# IA-prop-raspberry.net
KiCad netlist of a schematic drawn in EAGLE
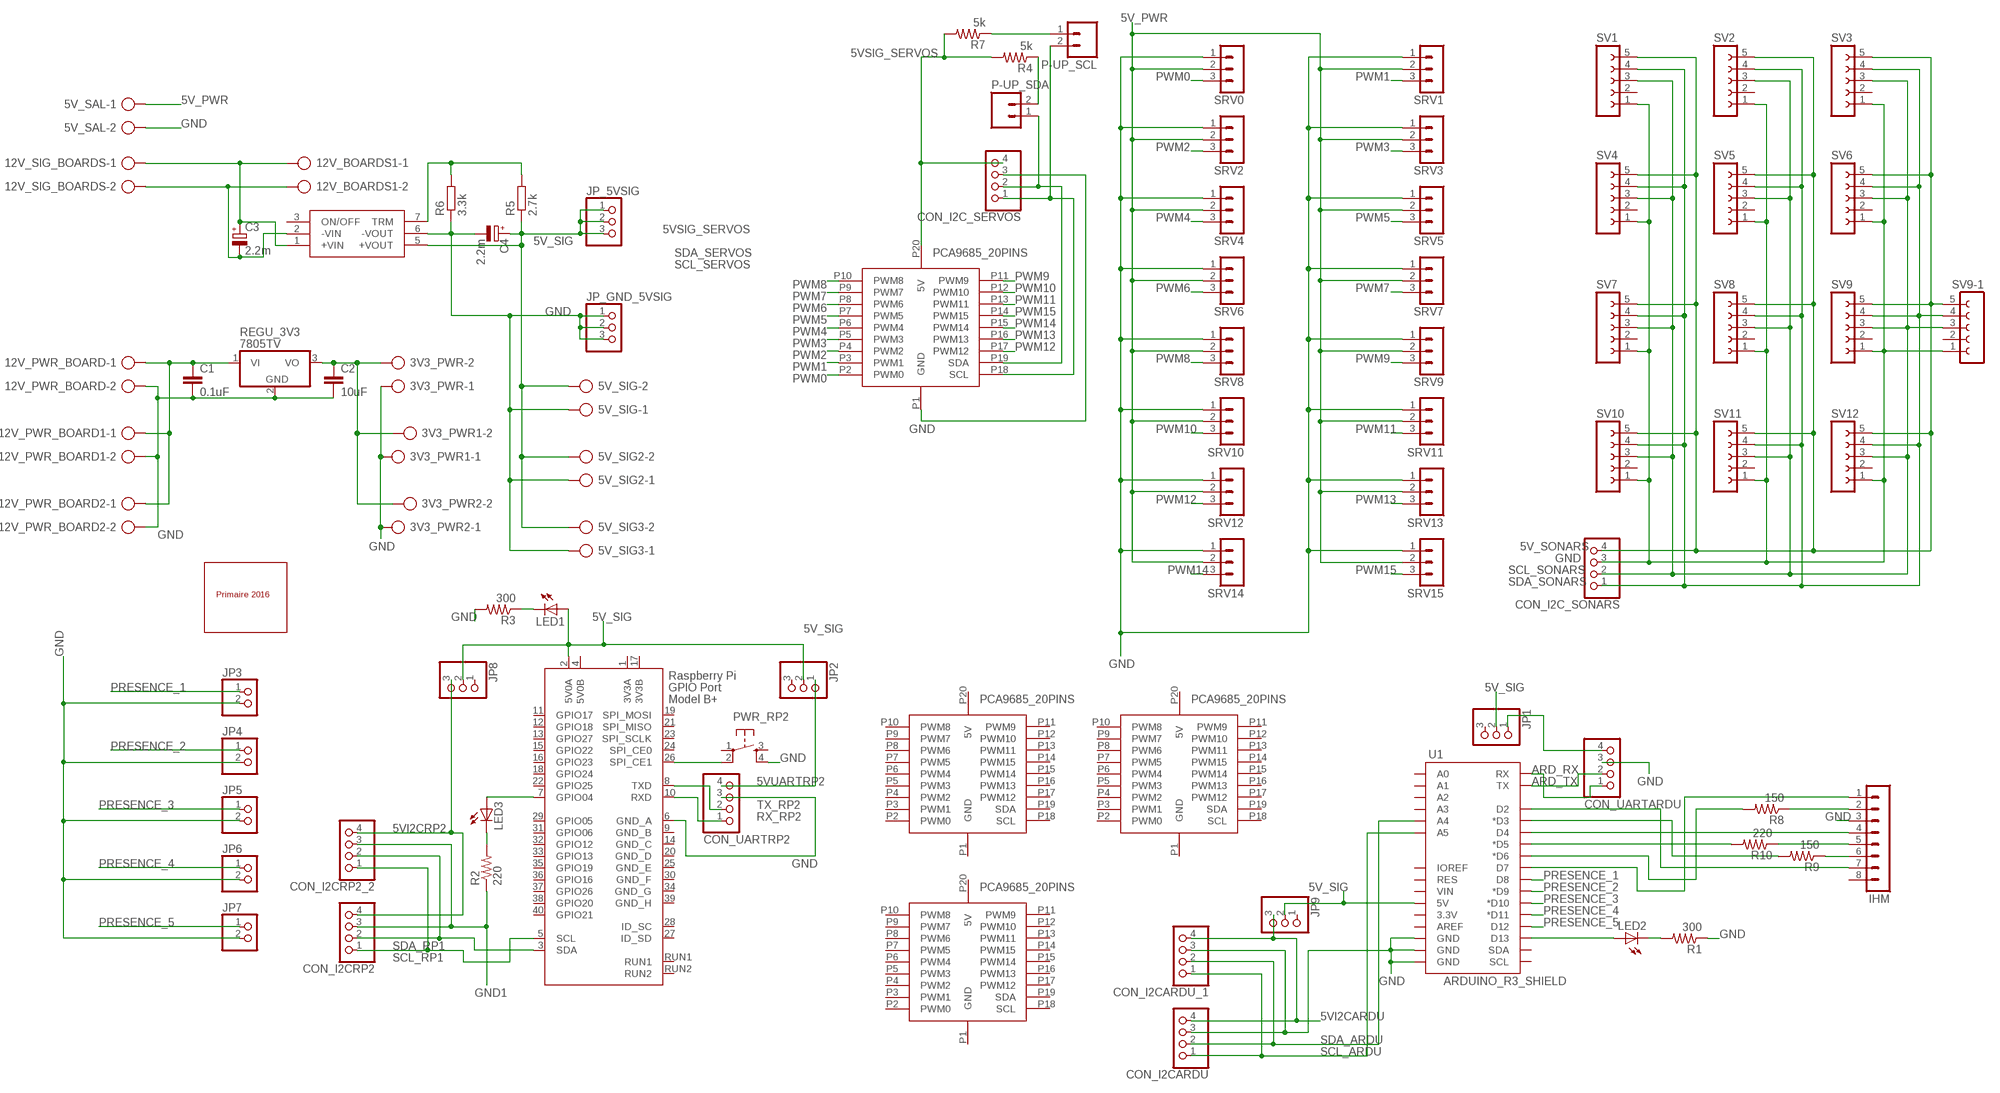
[diagram p0: schematic, sheet 1, part 1 of 2]
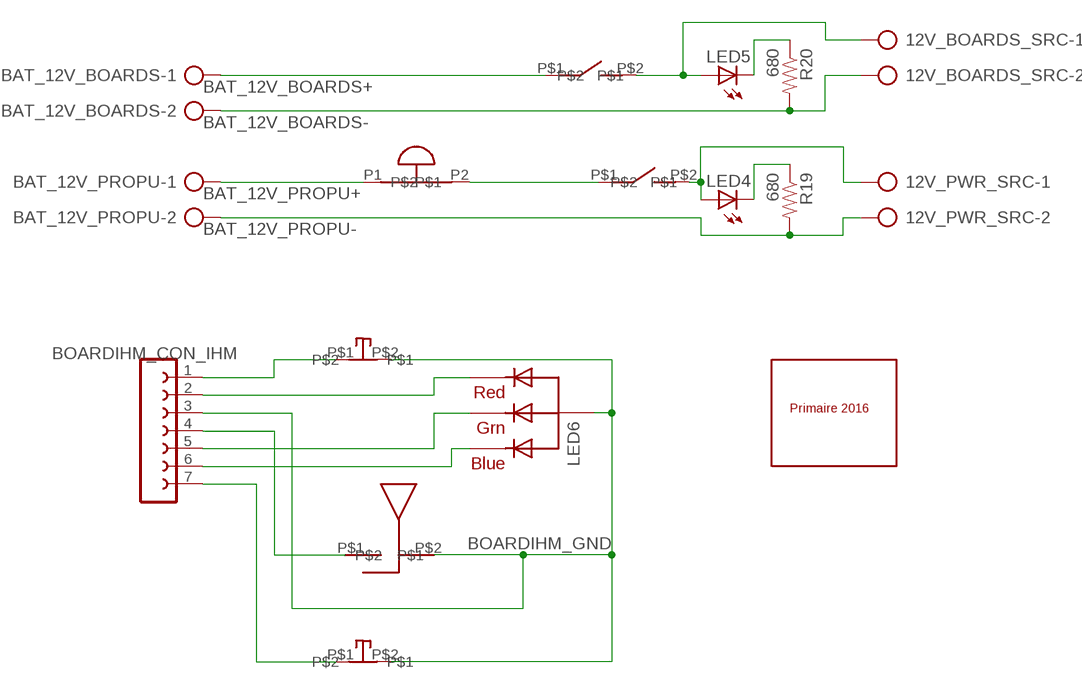
[diagram p1: schematic, sheet 1, part 2 of 2]

(export (version "E")
  (design (tool "Eeschema 10.0.6"))
  (components
    (comp (ref "3V3_PWR")
      (value "AK300/2")
      (footprint "eagle-import:AK300_2")
      (fields (field (name "OC_FARNELL") "unknown") (field (name "OC_NEWARK") "unknown"))
      (libsource (lib "eagle-import") (part "AK300/2"))
    )
    (comp (ref "3V3_PWR1")
      (value "AK300/2")
      (footprint "eagle-import:AK300_2")
      (fields (field (name "OC_FARNELL") "unknown") (field (name "OC_NEWARK") "unknown"))
      (libsource (lib "eagle-import") (part "AK300/2"))
    )
    (comp (ref "3V3_PWR2")
      (value "AK300/2")
      (footprint "eagle-import:AK300_2")
      (fields (field (name "OC_FARNELL") "unknown") (field (name "OC_NEWARK") "unknown"))
      (libsource (lib "eagle-import") (part "AK300/2"))
    )
    (comp (ref "5V_SAL")
      (value "AK300/2")
      (footprint "eagle-import:AK300_2")
      (fields (field (name "OC_FARNELL") "unknown") (field (name "OC_NEWARK") "unknown"))
      (libsource (lib "eagle-import") (part "AK300/2"))
    )
    (comp (ref "5V_SIG")
      (value "AK300/2")
      (footprint "eagle-import:AK300_2")
      (fields (field (name "OC_FARNELL") "unknown") (field (name "OC_NEWARK") "unknown"))
      (libsource (lib "eagle-import") (part "AK300/2"))
    )
    (comp (ref "5V_SIG2")
      (value "AK300/2")
      (footprint "eagle-import:AK300_2")
      (fields (field (name "OC_FARNELL") "unknown") (field (name "OC_NEWARK") "unknown"))
      (libsource (lib "eagle-import") (part "AK300/2"))
    )
    (comp (ref "5V_SIG3")
      (value "AK300/2")
      (footprint "eagle-import:AK300_2")
      (fields (field (name "OC_FARNELL") "unknown") (field (name "OC_NEWARK") "unknown"))
      (libsource (lib "eagle-import") (part "AK300/2"))
    )
    (comp (ref "12V_BOARDS1")
      (value "AK300/2")
      (footprint "eagle-import:AK300_2")
      (libsource (lib "eagle-import") (part "AK300/2"))
    )
    (comp (ref "12V_BOARDS_SRC")
      (value "AK300/2")
      (footprint "eagle-import:AK300_2")
      (fields (field (name "OC_FARNELL") "unknown") (field (name "OC_NEWARK") "unknown"))
      (libsource (lib "eagle-import") (part "AK300/2"))
    )
    (comp (ref "12V_PWR_BOARD")
      (value "AK300/2")
      (footprint "eagle-import:AK300_2")
      (fields (field (name "OC_FARNELL") "unknown") (field (name "OC_NEWARK") "unknown"))
      (libsource (lib "eagle-import") (part "AK300/2"))
    )
    (comp (ref "12V_PWR_BOARD1")
      (value "AK300/2")
      (footprint "eagle-import:AK300_2")
      (fields (field (name "OC_FARNELL") "unknown") (field (name "OC_NEWARK") "unknown"))
      (libsource (lib "eagle-import") (part "AK300/2"))
    )
    (comp (ref "12V_PWR_BOARD2")
      (value "AK300/2")
      (footprint "eagle-import:AK300_2")
      (libsource (lib "eagle-import") (part "AK300/2"))
    )
    (comp (ref "12V_PWR_SRC")
      (value "AK300/2")
      (footprint "eagle-import:AK300_2")
      (fields (field (name "OC_FARNELL") "unknown") (field (name "OC_NEWARK") "unknown"))
      (libsource (lib "eagle-import") (part "AK300/2"))
    )
    (comp (ref "12V_SIG_BOARDS")
      (value "AK300/2")
      (footprint "eagle-import:AK300_2")
      (libsource (lib "eagle-import") (part "AK300/2"))
    )
    (comp (ref "BAT_12V_BOARDS")
      (value "AK300/2")
      (footprint "eagle-import:AK300_2")
      (fields (field (name "OC_FARNELL") "unknown") (field (name "OC_NEWARK") "unknown"))
      (libsource (lib "eagle-import") (part "AK300/2"))
    )
    (comp (ref "BAT_12V_PROPU")
      (value "AK300/2")
      (footprint "eagle-import:AK300_2")
      (fields (field (name "OC_FARNELL") "unknown") (field (name "OC_NEWARK") "unknown"))
      (libsource (lib "eagle-import") (part "AK300/2"))
    )
    (comp (ref "BOARDIHM_CON_IHM")
      (value "FE07-1")
      (footprint "eagle-import:FE07")
      (libsource (lib "eagle-import") (part "FE07-1"))
    )
    (comp (ref "C1")
      (value "0.1uF")
      (footprint "eagle-import:C050-025X075")
      (libsource (lib "eagle-import") (part "C-EU050-025X075"))
    )
    (comp (ref "C2")
      (value "10uF")
      (footprint "eagle-import:C050-025X075")
      (libsource (lib "eagle-import") (part "C-EU050-025X075"))
    )
    (comp (ref "C3")
      (value "2.2m")
      (footprint "eagle-import:E5-13")
      (libsource (lib "eagle-import") (part "CPOL-EUE5-13"))
    )
    (comp (ref "C4")
      (value "2.2m")
      (footprint "eagle-import:E5-13")
      (libsource (lib "eagle-import") (part "CPOL-EUE5-13"))
    )
    (comp (ref "CON_I2CARDU")
      (value "PINHD-1X4")
      (footprint "eagle-import:1X04")
      (libsource (lib "eagle-import") (part "PINHD-1X4"))
    )
    (comp (ref "CON_I2CARDU_1")
      (value "PINHD-1X4")
      (footprint "eagle-import:1X04")
      (libsource (lib "eagle-import") (part "PINHD-1X4"))
    )
    (comp (ref "CON_I2CRP2")
      (value "PINHD-1X4")
      (footprint "eagle-import:1X04")
      (libsource (lib "eagle-import") (part "PINHD-1X4"))
    )
    (comp (ref "CON_I2CRP2_2")
      (value "PINHD-1X4")
      (footprint "eagle-import:1X04")
      (libsource (lib "eagle-import") (part "PINHD-1X4"))
    )
    (comp (ref "CON_I2C_SERVOS")
      (value "PINHD-1X4")
      (footprint "eagle-import:1X04")
      (libsource (lib "eagle-import") (part "PINHD-1X4"))
    )
    (comp (ref "CON_I2C_SONARS")
      (value "PINHD-1X4")
      (footprint "eagle-import:1X04")
      (libsource (lib "eagle-import") (part "PINHD-1X4"))
    )
    (comp (ref "CON_UARTARDU")
      (value "PINHD-1X4")
      (footprint "eagle-import:1X04")
      (libsource (lib "eagle-import") (part "PINHD-1X4"))
    )
    (comp (ref "CON_UARTRP2")
      (value "PINHD-1X4")
      (footprint "eagle-import:1X04")
      (libsource (lib "eagle-import") (part "PINHD-1X4"))
    )
    (comp (ref "IHM")
      (value "MA08-1")
      (footprint "eagle-import:MA08-1")
      (libsource (lib "eagle-import") (part "MA08-1"))
    )
    (comp (ref "JP1")
      (value "PINHD-1X3")
      (footprint "eagle-import:1X03")
      (libsource (lib "eagle-import") (part "PINHD-1X3"))
    )
    (comp (ref "JP2")
      (value "PINHD-1X3")
      (footprint "eagle-import:1X03")
      (libsource (lib "eagle-import") (part "PINHD-1X3"))
    )
    (comp (ref "JP3")
      (value "PINHD-1X2")
      (footprint "eagle-import:1X02")
      (libsource (lib "eagle-import") (part "PINHD-1X2"))
    )
    (comp (ref "JP4")
      (value "PINHD-1X2")
      (footprint "eagle-import:1X02")
      (libsource (lib "eagle-import") (part "PINHD-1X2"))
    )
    (comp (ref "JP5")
      (value "PINHD-1X2")
      (footprint "eagle-import:1X02")
      (libsource (lib "eagle-import") (part "PINHD-1X2"))
    )
    (comp (ref "JP6")
      (value "PINHD-1X2")
      (footprint "eagle-import:1X02")
      (libsource (lib "eagle-import") (part "PINHD-1X2"))
    )
    (comp (ref "JP7")
      (value "PINHD-1X2")
      (footprint "eagle-import:1X02")
      (libsource (lib "eagle-import") (part "PINHD-1X2"))
    )
    (comp (ref "JP8")
      (value "PINHD-1X3")
      (footprint "eagle-import:1X03")
      (libsource (lib "eagle-import") (part "PINHD-1X3"))
    )
    (comp (ref "JP9")
      (value "PINHD-1X3")
      (footprint "eagle-import:1X03")
      (libsource (lib "eagle-import") (part "PINHD-1X3"))
    )
    (comp (ref "JP_5VSIG")
      (value "PINHD-1X3")
      (footprint "eagle-import:1X03")
      (libsource (lib "eagle-import") (part "PINHD-1X3"))
    )
    (comp (ref "JP_GND_5VSIG")
      (value "PINHD-1X3")
      (footprint "eagle-import:1X03")
      (libsource (lib "eagle-import") (part "PINHD-1X3"))
    )
    (comp (ref "LED1")
      (value "LED3MM")
      (footprint "eagle-import:LED3MM")
      (libsource (lib "eagle-import") (part "LED3MM"))
    )
    (comp (ref "LED2")
      (value "LED3MM")
      (footprint "eagle-import:LED3MM")
      (libsource (lib "eagle-import") (part "LED3MM"))
    )
    (comp (ref "LED3")
      (value "LED3MM")
      (footprint "eagle-import:LED3MM")
      (libsource (lib "eagle-import") (part "LED3MM"))
    )
    (comp (ref "LED4")
      (value "LED5MM")
      (footprint "eagle-import:LED5MM")
      (libsource (lib "eagle-import") (part "adafruit_LED5MM"))
    )
    (comp (ref "LED5")
      (value "LED5MM")
      (footprint "eagle-import:LED5MM")
      (libsource (lib "eagle-import") (part "adafruit_LED5MM"))
    )
    (comp (ref "LED6")
      (value "RGBLED_CA-5MM")
      (footprint "eagle-import:LED5MMRGB")
      (libsource (lib "eagle-import") (part "RGBLED_CA-5MM"))
    )
    (comp (ref "P-UP_SCL")
      (value "M02PTH")
      (footprint "eagle-import:1X02")
      (libsource (lib "eagle-import") (part "M02PTH"))
    )
    (comp (ref "P-UP_SDA")
      (value "M02PTH")
      (footprint "eagle-import:1X02")
      (libsource (lib "eagle-import") (part "M02PTH"))
    )
    (comp (ref "PWR_RP2")
      (value "TAC_SWITCHPTH")
      (footprint "eagle-import:TACTILE-PTH")
      (libsource (lib "eagle-import") (part "TAC_SWITCHPTH"))
    )
    (comp (ref "R1")
      (value "300")
      (footprint "eagle-import:AXIAL-0.3")
      (libsource (lib "eagle-import") (part "RESISTORAXIAL-0.3"))
    )
    (comp (ref "R2")
      (value "220")
      (footprint "eagle-import:AXIAL-0.3")
      (libsource (lib "eagle-import") (part "RESISTORAXIAL-0.3"))
    )
    (comp (ref "R3")
      (value "300")
      (footprint "eagle-import:AXIAL-0.3")
      (libsource (lib "eagle-import") (part "RESISTORAXIAL-0.3"))
    )
    (comp (ref "R4")
      (value "5k")
      (footprint "eagle-import:AXIAL-0.3")
      (libsource (lib "eagle-import") (part "RESISTORAXIAL-0.3"))
    )
    (comp (ref "R5")
      (value "2.7k")
      (footprint "eagle-import:0207_7")
      (libsource (lib "eagle-import") (part "R-EU_0207/7"))
    )
    (comp (ref "R6")
      (value "3.3k")
      (footprint "eagle-import:0207_7")
      (libsource (lib "eagle-import") (part "R-EU_0207/7"))
    )
    (comp (ref "R7")
      (value "5k")
      (footprint "eagle-import:AXIAL-0.3")
      (libsource (lib "eagle-import") (part "RESISTORAXIAL-0.3"))
    )
    (comp (ref "R8")
      (value "150")
      (footprint "eagle-import:AXIAL-0.3")
      (libsource (lib "eagle-import") (part "RESISTORAXIAL-0.3"))
    )
    (comp (ref "R9")
      (value "150")
      (footprint "eagle-import:AXIAL-0.3")
      (libsource (lib "eagle-import") (part "RESISTORAXIAL-0.3"))
    )
    (comp (ref "R10")
      (value "220")
      (footprint "eagle-import:AXIAL-0.3")
      (libsource (lib "eagle-import") (part "RESISTORAXIAL-0.3"))
    )
    (comp (ref "R19")
      (value "680")
      (footprint "eagle-import:AXIAL-0.3")
      (libsource (lib "eagle-import") (part "RESISTORAXIAL-0.3"))
    )
    (comp (ref "R20")
      (value "680")
      (footprint "eagle-import:AXIAL-0.3")
      (libsource (lib "eagle-import") (part "RESISTORAXIAL-0.3"))
    )
    (comp (ref "REGU_3V3")
      (value "7805TV")
      (footprint "eagle-import:TO220V")
      (libsource (lib "eagle-import") (part "78TV05"))
    )
    (comp (ref "RP2")
      (value "RASPI_BOARD_B+#_FP")
      (footprint "eagle-import:RASPI_BOARD_B+_FULL_PAD")
      (libsource (lib "eagle-import") (part "RASPI_BOARD_B+#_FP"))
    )
    (comp (ref "SRV0")
      (value "MA03-1")
      (footprint "eagle-import:MA03-1")
      (libsource (lib "eagle-import") (part "MA03-1"))
    )
    (comp (ref "SRV1")
      (value "MA03-1")
      (footprint "eagle-import:MA03-1")
      (libsource (lib "eagle-import") (part "MA03-1"))
    )
    (comp (ref "SRV2")
      (value "MA03-1")
      (footprint "eagle-import:MA03-1")
      (libsource (lib "eagle-import") (part "MA03-1"))
    )
    (comp (ref "SRV3")
      (value "MA03-1")
      (footprint "eagle-import:MA03-1")
      (libsource (lib "eagle-import") (part "MA03-1"))
    )
    (comp (ref "SRV4")
      (value "MA03-1")
      (footprint "eagle-import:MA03-1")
      (libsource (lib "eagle-import") (part "MA03-1"))
    )
    (comp (ref "SRV5")
      (value "MA03-1")
      (footprint "eagle-import:MA03-1")
      (libsource (lib "eagle-import") (part "MA03-1"))
    )
    (comp (ref "SRV6")
      (value "MA03-1")
      (footprint "eagle-import:MA03-1")
      (libsource (lib "eagle-import") (part "MA03-1"))
    )
    (comp (ref "SRV7")
      (value "MA03-1")
      (footprint "eagle-import:MA03-1")
      (libsource (lib "eagle-import") (part "MA03-1"))
    )
    (comp (ref "SRV8")
      (value "MA03-1")
      (footprint "eagle-import:MA03-1")
      (libsource (lib "eagle-import") (part "MA03-1"))
    )
    (comp (ref "SRV9")
      (value "MA03-1")
      (footprint "eagle-import:MA03-1")
      (libsource (lib "eagle-import") (part "MA03-1"))
    )
    (comp (ref "SRV10")
      (value "MA03-1")
      (footprint "eagle-import:MA03-1")
      (libsource (lib "eagle-import") (part "MA03-1"))
    )
    (comp (ref "SRV11")
      (value "MA03-1")
      (footprint "eagle-import:MA03-1")
      (libsource (lib "eagle-import") (part "MA03-1"))
    )
    (comp (ref "SRV12")
      (value "MA03-1")
      (footprint "eagle-import:MA03-1")
      (libsource (lib "eagle-import") (part "MA03-1"))
    )
    (comp (ref "SRV13")
      (value "MA03-1")
      (footprint "eagle-import:MA03-1")
      (libsource (lib "eagle-import") (part "MA03-1"))
    )
    (comp (ref "SRV14")
      (value "MA03-1")
      (footprint "eagle-import:MA03-1")
      (libsource (lib "eagle-import") (part "MA03-1"))
    )
    (comp (ref "SRV15")
      (value "MA03-1")
      (footprint "eagle-import:MA03-1")
      (libsource (lib "eagle-import") (part "MA03-1"))
    )
    (comp (ref "SV1")
      (value "FE05-1")
      (footprint "eagle-import:FE05-1")
      (libsource (lib "eagle-import") (part "FE05-1"))
    )
    (comp (ref "SV2")
      (value "FE05-1")
      (footprint "eagle-import:FE05-1")
      (fields (field (name "OC_FARNELL") "unknown") (field (name "OC_NEWARK") "unknown"))
      (libsource (lib "eagle-import") (part "FE05-1"))
    )
    (comp (ref "SV3")
      (value "FE05-1")
      (footprint "eagle-import:FE05-1")
      (fields (field (name "OC_FARNELL") "unknown") (field (name "OC_NEWARK") "unknown"))
      (libsource (lib "eagle-import") (part "FE05-1"))
    )
    (comp (ref "SV4")
      (value "FE05-1")
      (footprint "eagle-import:FE05-1")
      (libsource (lib "eagle-import") (part "FE05-1"))
    )
    (comp (ref "SV5")
      (value "FE05-1")
      (footprint "eagle-import:FE05-1")
      (fields (field (name "OC_FARNELL") "unknown") (field (name "OC_NEWARK") "unknown"))
      (libsource (lib "eagle-import") (part "FE05-1"))
    )
    (comp (ref "SV6")
      (value "FE05-1")
      (footprint "eagle-import:FE05-1")
      (fields (field (name "OC_FARNELL") "unknown") (field (name "OC_NEWARK") "unknown"))
      (libsource (lib "eagle-import") (part "FE05-1"))
    )
    (comp (ref "SV7")
      (value "FE05-1")
      (footprint "eagle-import:FE05-1")
      (libsource (lib "eagle-import") (part "FE05-1"))
    )
    (comp (ref "SV8")
      (value "FE05-1")
      (footprint "eagle-import:FE05-1")
      (fields (field (name "OC_FARNELL") "unknown") (field (name "OC_NEWARK") "unknown"))
      (libsource (lib "eagle-import") (part "FE05-1"))
    )
    (comp (ref "SV9")
      (value "FE05-1")
      (footprint "eagle-import:FE05-1")
      (fields (field (name "OC_FARNELL") "unknown") (field (name "OC_NEWARK") "unknown"))
      (libsource (lib "eagle-import") (part "FE05-1"))
    )
    (comp (ref "SV9-1")
      (value "FE05-1")
      (footprint "eagle-import:FE05-1")
      (libsource (lib "eagle-import") (part "FE05-1"))
    )
    (comp (ref "SV10")
      (value "FE05-1")
      (footprint "eagle-import:FE05-1")
      (libsource (lib "eagle-import") (part "FE05-1"))
    )
    (comp (ref "SV11")
      (value "FE05-1")
      (footprint "eagle-import:FE05-1")
      (fields (field (name "OC_FARNELL") "unknown") (field (name "OC_NEWARK") "unknown"))
      (libsource (lib "eagle-import") (part "FE05-1"))
    )
    (comp (ref "SV12")
      (value "FE05-1")
      (footprint "eagle-import:FE05-1")
      (fields (field (name "OC_FARNELL") "unknown") (field (name "OC_NEWARK") "unknown"))
      (libsource (lib "eagle-import") (part "FE05-1"))
    )
    (comp (ref "U$1")
      (value "PCA9685_FEMALE")
      (footprint "eagle-import:2X10PINS_SPACE10MM")
      (libsource (lib "eagle-import") (part "PCA9685_FEMALE"))
    )
    (comp (ref "U$2")
      (value "TEN25-1211TEN25-1211")
      (footprint "eagle-import:TEN25")
      (libsource (lib "eagle-import") (part "TEN25-1211TEN25-1211"))
    )
    (comp (ref "U$3")
      (value "FOOTPRINT_PRIMAIRE2016")
      (footprint "eagle-import:PRIMAIRE2016")
      (libsource (lib "eagle-import") (part "FOOTPRINT_PRIMAIRE2016"))
    )
    (comp (ref "U$4")
      (value "BAU")
      (footprint "eagle-import:BAU_30")
      (libsource (lib "eagle-import") (part "BAU"))
    )
    (comp (ref "U$5")
      (value "PCA9685_MALE")
      (footprint "eagle-import:TSSOP28_&_2X10PINS_SPACE10MM")
      (libsource (lib "eagle-import") (part "PCA9685_MALE"))
    )
    (comp (ref "U$6")
      (value "SWITCH_01")
      (footprint "eagle-import:SWITCH_01")
      (libsource (lib "eagle-import") (part "SWITCH_01"))
    )
    (comp (ref "U$7")
      (value "PCA9685_MALE")
      (footprint "eagle-import:TSSOP28_&_2X10PINS_SPACE10MM")
      (libsource (lib "eagle-import") (part "PCA9685_MALE"))
    )
    (comp (ref "U$8")
      (value "SWITCH_01")
      (footprint "eagle-import:SWITCH_01")
      (libsource (lib "eagle-import") (part "SWITCH_01"))
    )
    (comp (ref "U$9")
      (value "PUSH_BUT_COL_SELEC")
      (footprint "eagle-import:PUSH_BUT_COL_SELEC")
      (libsource (lib "eagle-import") (part "PUSH_BUT_COL_SELEC"))
    )
    (comp (ref "U$10")
      (value "CORD")
      (footprint "eagle-import:CORD")
      (libsource (lib "eagle-import") (part "CORD"))
    )
    (comp (ref "U$11")
      (value "FOOTPRINT_PRIMAIRE2016")
      (footprint "eagle-import:PRIMAIRE2016")
      (libsource (lib "eagle-import") (part "FOOTPRINT_PRIMAIRE2016"))
    )
    (comp (ref "U$12")
      (value "PUSH_BUT_COL_SELEC")
      (footprint "eagle-import:PUSH_BUT_COL_SELEC")
      (libsource (lib "eagle-import") (part "PUSH_BUT_COL_SELEC"))
    )
    (comp (ref "U$13")
      (value "PCA9685_MALE")
      (footprint "eagle-import:TSSOP28_&_2X10PINS_SPACE10MM")
      (libsource (lib "eagle-import") (part "PCA9685_MALE"))
    )
    (comp (ref "U1")
      (value "ARDUINO_R3_SHIELD")
      (footprint "eagle-import:UNO_R3_SHIELD")
      (libsource (lib "eagle-import") (part "ARDUINO_R3_SHIELD"))
    )
  )
  (nets
    (net (code "1") (name "/3V3A") (class "Default")
      (node (ref "RP2") (pin "1") (pinfunction "3V3A_1") (pintype "power_in"))
    )
    (net (code "2") (name "/3V3B") (class "Default")
      (node (ref "RP2") (pin "17") (pinfunction "3V3B_17") (pintype "power_in"))
    )
    (net (code "3") (name "/5V0B") (class "Default")
      (node (ref "RP2") (pin "4") (pinfunction "5V0B_4") (pintype "power_in"))
    )
    (net (code "4") (name "/5VI2CARDU") (class "Default")
      (node (ref "CON_I2CARDU") (pin "4") (pinfunction "4_4") (pintype "passive"))
      (node (ref "CON_I2CARDU_1") (pin "4") (pinfunction "4_4") (pintype "passive"))
      (node (ref "JP9") (pin "3") (pinfunction "3_3") (pintype "passive"))
    )
    (net (code "5") (name "/5VI2CRP2") (class "Default")
      (node (ref "CON_I2CRP2") (pin "4") (pinfunction "4_4") (pintype "passive"))
      (node (ref "CON_I2CRP2_2") (pin "4") (pinfunction "4_4") (pintype "passive"))
      (node (ref "JP8") (pin "3") (pinfunction "3_3") (pintype "passive"))
    )
    (net (code "6") (name "/5VSIG_SERVOS") (class "Default")
      (node (ref "CON_I2C_SERVOS") (pin "4") (pinfunction "4_4") (pintype "passive"))
      (node (ref "R4") (pin "P$2") (pinfunction "2_P$2") (pintype "passive"))
      (node (ref "R7") (pin "P$2") (pinfunction "2_P$2") (pintype "passive"))
      (node (ref "U$1") (pin "P20") (pinfunction "5V_P20") (pintype "bidirectional"))
    )
    (net (code "7") (name "/5VUARTRP2") (class "Default")
      (node (ref "CON_UARTRP2") (pin "4") (pinfunction "4_4") (pintype "passive"))
      (node (ref "JP2") (pin "1") (pinfunction "1_1") (pintype "passive"))
    )
    (net (code "8") (name "/5V_PWR") (class "Default")
      (node (ref "5V_SAL") (pin "1") (pinfunction "KL_1") (pintype "passive"))
      (node (ref "SRV0") (pin "2") (pinfunction "2_2") (pintype "passive"))
      (node (ref "SRV1") (pin "2") (pinfunction "2_2") (pintype "passive"))
      (node (ref "SRV10") (pin "2") (pinfunction "2_2") (pintype "passive"))
      (node (ref "SRV11") (pin "2") (pinfunction "2_2") (pintype "passive"))
      (node (ref "SRV12") (pin "2") (pinfunction "2_2") (pintype "passive"))
      (node (ref "SRV13") (pin "2") (pinfunction "2_2") (pintype "passive"))
      (node (ref "SRV14") (pin "2") (pinfunction "2_2") (pintype "passive"))
      (node (ref "SRV15") (pin "2") (pinfunction "2_2") (pintype "passive"))
      (node (ref "SRV2") (pin "2") (pinfunction "2_2") (pintype "passive"))
      (node (ref "SRV3") (pin "2") (pinfunction "2_2") (pintype "passive"))
      (node (ref "SRV4") (pin "2") (pinfunction "2_2") (pintype "passive"))
      (node (ref "SRV5") (pin "2") (pinfunction "2_2") (pintype "passive"))
      (node (ref "SRV6") (pin "2") (pinfunction "2_2") (pintype "passive"))
      (node (ref "SRV7") (pin "2") (pinfunction "2_2") (pintype "passive"))
      (node (ref "SRV8") (pin "2") (pinfunction "2_2") (pintype "passive"))
      (node (ref "SRV9") (pin "2") (pinfunction "2_2") (pintype "passive"))
    )
    (net (code "9") (name "/5V_SIG") (class "Default")
      (node (ref "5V_SIG") (pin "2") (pinfunction "KL_2") (pintype "passive"))
      (node (ref "5V_SIG2") (pin "2") (pinfunction "KL_2") (pintype "passive"))
      (node (ref "5V_SIG3") (pin "2") (pinfunction "KL_2") (pintype "passive"))
      (node (ref "C4") (pin "+") (pinfunction "+_+") (pintype "passive"))
      (node (ref "JP1") (pin "2") (pinfunction "2_2") (pintype "passive"))
      (node (ref "JP2") (pin "2") (pinfunction "2_2") (pintype "passive"))
      (node (ref "JP8") (pin "2") (pinfunction "2_2") (pintype "passive"))
      (node (ref "JP9") (pin "2") (pinfunction "2_2") (pintype "passive"))
      (node (ref "JP_5VSIG") (pin "1") (pinfunction "1_1") (pintype "passive"))
      (node (ref "JP_5VSIG") (pin "2") (pinfunction "2_2") (pintype "passive"))
      (node (ref "JP_5VSIG") (pin "3") (pinfunction "3_3") (pintype "passive"))
      (node (ref "LED1") (pin "A") (pinfunction "A_A") (pintype "passive"))
      (node (ref "R5") (pin "1") (pinfunction "1_1") (pintype "passive"))
      (node (ref "RP2") (pin "2") (pinfunction "5V0A_2") (pintype "power_in"))
      (node (ref "U$2") (pin "5") (pinfunction "+VOUT_5") (pintype "bidirectional"))
      (node (ref "U1") (pin "5V") (pinfunction "5V_5V") (pintype "bidirectional"))
    )
    (net (code "10") (name "/5V_SONARS") (class "Default")
      (node (ref "CON_I2C_SONARS") (pin "4") (pinfunction "4_4") (pintype "passive"))
      (node (ref "SV1") (pin "5") (pinfunction "5_5") (pintype "passive"))
      (node (ref "SV10") (pin "5") (pinfunction "5_5") (pintype "passive"))
      (node (ref "SV11") (pin "5") (pinfunction "5_5") (pintype "passive"))
      (node (ref "SV12") (pin "5") (pinfunction "5_5") (pintype "passive"))
      (node (ref "SV2") (pin "5") (pinfunction "5_5") (pintype "passive"))
      (node (ref "SV3") (pin "5") (pinfunction "5_5") (pintype "passive"))
      (node (ref "SV4") (pin "5") (pinfunction "5_5") (pintype "passive"))
      (node (ref "SV5") (pin "5") (pinfunction "5_5") (pintype "passive"))
      (node (ref "SV6") (pin "5") (pinfunction "5_5") (pintype "passive"))
      (node (ref "SV7") (pin "5") (pinfunction "5_5") (pintype "passive"))
      (node (ref "SV8") (pin "5") (pinfunction "5_5") (pintype "passive"))
      (node (ref "SV9") (pin "5") (pinfunction "5_5") (pintype "passive"))
      (node (ref "SV9-1") (pin "5") (pinfunction "5_5") (pintype "passive"))
    )
    (net (code "11") (name "/ARD_RX") (class "Default")
      (node (ref "CON_UARTARDU") (pin "1") (pinfunction "1_1") (pintype "passive"))
      (node (ref "U1") (pin "RX") (pinfunction "RX_RX") (pintype "bidirectional"))
    )
    (net (code "12") (name "/ARD_TX") (class "Default")
      (node (ref "CON_UARTARDU") (pin "2") (pinfunction "2_2") (pintype "passive"))
      (node (ref "U1") (pin "TX") (pinfunction "TX_TX") (pintype "bidirectional"))
    )
    (net (code "13") (name "/BAT_12V_BOARDS+") (class "Default")
      (node (ref "BAT_12V_BOARDS") (pin "1") (pinfunction "KL_1") (pintype "passive"))
      (node (ref "U$8") (pin "P$1") (pinfunction "P$1_P$1") (pintype "bidirectional"))
    )
    (net (code "14") (name "/BAT_12V_BOARDS-") (class "Default")
      (node (ref "12V_BOARDS_SRC") (pin "2") (pinfunction "KL_2") (pintype "passive"))
      (node (ref "BAT_12V_BOARDS") (pin "2") (pinfunction "KL_2") (pintype "passive"))
      (node (ref "R20") (pin "P$2") (pinfunction "2_P$2") (pintype "passive"))
    )
    (net (code "15") (name "/BAT_12V_PROPU+") (class "Default")
      (node (ref "BAT_12V_PROPU") (pin "1") (pinfunction "KL_1") (pintype "passive"))
      (node (ref "U$4") (pin "P1") (pinfunction "P$1_P1") (pintype "bidirectional"))
    )
    (net (code "16") (name "/BAT_12V_PROPU-") (class "Default")
      (node (ref "12V_PWR_SRC") (pin "2") (pinfunction "KL_2") (pintype "passive"))
      (node (ref "BAT_12V_PROPU") (pin "2") (pinfunction "KL_2") (pintype "passive"))
      (node (ref "R19") (pin "P$2") (pinfunction "2_P$2") (pintype "passive"))
    )
    (net (code "17") (name "/BOARDIHM_GND") (class "Default")
      (node (ref "BOARDIHM_CON_IHM") (pin "3") (pinfunction "3_3") (pintype "passive"))
      (node (ref "LED6") (pin "2") (pinfunction "VCC_2") (pintype "bidirectional"))
      (node (ref "U$10") (pin "P$2") (pinfunction "P$2_P$2") (pintype "bidirectional"))
      (node (ref "U$12") (pin "P$2") (pinfunction "P$2_P$2") (pintype "bidirectional"))
      (node (ref "U$9") (pin "P$2") (pinfunction "P$2_P$2") (pintype "bidirectional"))
    )
    (net (code "18") (name "/GND") (class "Default")
      (node (ref "12V_PWR_BOARD") (pin "2") (pinfunction "KL_2") (pintype "passive"))
      (node (ref "12V_PWR_BOARD1") (pin "2") (pinfunction "KL_2") (pintype "passive"))
      (node (ref "12V_PWR_BOARD2") (pin "2") (pinfunction "KL_2") (pintype "passive"))
      (node (ref "3V3_PWR") (pin "1") (pinfunction "KL_1") (pintype "passive"))
      (node (ref "3V3_PWR1") (pin "1") (pinfunction "KL_1") (pintype "passive"))
      (node (ref "3V3_PWR2") (pin "1") (pinfunction "KL_1") (pintype "passive"))
      (node (ref "5V_SAL") (pin "2") (pinfunction "KL_2") (pintype "passive"))
      (node (ref "5V_SIG") (pin "1") (pinfunction "KL_1") (pintype "passive"))
      (node (ref "5V_SIG2") (pin "1") (pinfunction "KL_1") (pintype "passive"))
      (node (ref "5V_SIG3") (pin "1") (pinfunction "KL_1") (pintype "passive"))
      (node (ref "C1") (pin "2") (pinfunction "2_2") (pintype "passive"))
      (node (ref "C2") (pin "2") (pinfunction "2_2") (pintype "passive"))
      (node (ref "C4") (pin "-") (pinfunction "-_-") (pintype "passive"))
      (node (ref "CON_I2CARDU") (pin "3") (pinfunction "3_3") (pintype "passive"))
      (node (ref "CON_I2CARDU_1") (pin "3") (pinfunction "3_3") (pintype "passive"))
      (node (ref "CON_I2C_SERVOS") (pin "3") (pinfunction "3_3") (pintype "passive"))
      (node (ref "CON_I2C_SONARS") (pin "3") (pinfunction "3_3") (pintype "passive"))
      (node (ref "CON_UARTARDU") (pin "3") (pinfunction "3_3") (pintype "passive"))
      (node (ref "CON_UARTRP2") (pin "3") (pinfunction "3_3") (pintype "passive"))
      (node (ref "IHM") (pin "3") (pinfunction "3_3") (pintype "passive"))
      (node (ref "JP3") (pin "2") (pinfunction "2_2") (pintype "passive"))
      (node (ref "JP4") (pin "2") (pinfunction "2_2") (pintype "passive"))
      (node (ref "JP5") (pin "2") (pinfunction "2_2") (pintype "passive"))
      (node (ref "JP6") (pin "2") (pinfunction "2_2") (pintype "passive"))
      (node (ref "JP7") (pin "2") (pinfunction "2_2") (pintype "passive"))
      (node (ref "JP_GND_5VSIG") (pin "1") (pinfunction "1_1") (pintype "passive"))
      (node (ref "JP_GND_5VSIG") (pin "2") (pinfunction "2_2") (pintype "passive"))
      (node (ref "JP_GND_5VSIG") (pin "3") (pinfunction "3_3") (pintype "passive"))
      (node (ref "PWR_RP2") (pin "4") (pinfunction "4_4") (pintype "passive"))
      (node (ref "R1") (pin "P$1") (pinfunction "1_P$1") (pintype "passive"))
      (node (ref "R3") (pin "P$2") (pinfunction "2_P$2") (pintype "passive"))
      (node (ref "R6") (pin "1") (pinfunction "1_1") (pintype "passive"))
      (node (ref "REGU_3V3") (pin "2") (pinfunction "GND_2") (pintype "passive"))
      (node (ref "RP2") (pin "6") (pinfunction "GND_A_6") (pintype "power_in"))
      (node (ref "SRV0") (pin "1") (pinfunction "1_1") (pintype "passive"))
      (node (ref "SRV1") (pin "1") (pinfunction "1_1") (pintype "passive"))
      (node (ref "SRV10") (pin "1") (pinfunction "1_1") (pintype "passive"))
      (node (ref "SRV11") (pin "1") (pinfunction "1_1") (pintype "passive"))
      (node (ref "SRV12") (pin "1") (pinfunction "1_1") (pintype "passive"))
      (node (ref "SRV13") (pin "1") (pinfunction "1_1") (pintype "passive"))
      (node (ref "SRV14") (pin "1") (pinfunction "1_1") (pintype "passive"))
      (node (ref "SRV15") (pin "1") (pinfunction "1_1") (pintype "passive"))
      (node (ref "SRV2") (pin "1") (pinfunction "1_1") (pintype "passive"))
      (node (ref "SRV3") (pin "1") (pinfunction "1_1") (pintype "passive"))
      (node (ref "SRV4") (pin "1") (pinfunction "1_1") (pintype "passive"))
      (node (ref "SRV5") (pin "1") (pinfunction "1_1") (pintype "passive"))
      (node (ref "SRV6") (pin "1") (pinfunction "1_1") (pintype "passive"))
      (node (ref "SRV7") (pin "1") (pinfunction "1_1") (pintype "passive"))
      (node (ref "SRV8") (pin "1") (pinfunction "1_1") (pintype "passive"))
      (node (ref "SRV9") (pin "1") (pinfunction "1_1") (pintype "passive"))
      (node (ref "SV1") (pin "1") (pinfunction "1_1") (pintype "passive"))
      (node (ref "SV10") (pin "1") (pinfunction "1_1") (pintype "passive"))
      (node (ref "SV11") (pin "1") (pinfunction "1_1") (pintype "passive"))
      (node (ref "SV12") (pin "1") (pinfunction "1_1") (pintype "passive"))
      (node (ref "SV2") (pin "1") (pinfunction "1_1") (pintype "passive"))
      (node (ref "SV3") (pin "1") (pinfunction "1_1") (pintype "passive"))
      (node (ref "SV4") (pin "1") (pinfunction "1_1") (pintype "passive"))
      (node (ref "SV5") (pin "1") (pinfunction "1_1") (pintype "passive"))
      (node (ref "SV6") (pin "1") (pinfunction "1_1") (pintype "passive"))
      (node (ref "SV7") (pin "1") (pinfunction "1_1") (pintype "passive"))
      (node (ref "SV8") (pin "1") (pinfunction "1_1") (pintype "passive"))
      (node (ref "SV9") (pin "1") (pinfunction "1_1") (pintype "passive"))
      (node (ref "SV9-1") (pin "1") (pinfunction "1_1") (pintype "passive"))
      (node (ref "U$1") (pin "P1") (pinfunction "GND_P1") (pintype "bidirectional"))
      (node (ref "U$2") (pin "6") (pinfunction "-VOUT_6") (pintype "bidirectional"))
      (node (ref "U1") (pin "GND@0") (pinfunction "GND_GND@0") (pintype "bidirectional"))
      (node (ref "U1") (pin "GND@1") (pinfunction "GND_GND@1") (pintype "bidirectional"))
      (node (ref "U1") (pin "GND@2") (pinfunction "GND_GND@2") (pintype "bidirectional"))
    )
    (net (code "19") (name "/GND1") (class "Default")
      (node (ref "CON_I2CRP2") (pin "3") (pinfunction "3_3") (pintype "passive"))
      (node (ref "CON_I2CRP2_2") (pin "3") (pinfunction "3_3") (pintype "passive"))
      (node (ref "R2") (pin "P$1") (pinfunction "1_P$1") (pintype "passive"))
    )
    (net (code "20") (name "/GND_B") (class "Default")
      (node (ref "RP2") (pin "9") (pinfunction "GND_B_9") (pintype "power_in"))
    )
    (net (code "21") (name "/GND_C") (class "Default")
      (node (ref "RP2") (pin "14") (pinfunction "GND_C_14") (pintype "power_in"))
    )
    (net (code "22") (name "/GND_D") (class "Default")
      (node (ref "RP2") (pin "20") (pinfunction "GND_D_20") (pintype "power_in"))
    )
    (net (code "23") (name "/GND_E") (class "Default")
      (node (ref "RP2") (pin "25") (pinfunction "GND_E_25") (pintype "power_in"))
    )
    (net (code "24") (name "/GND_F") (class "Default")
      (node (ref "RP2") (pin "30") (pinfunction "GND_F_30") (pintype "power_in"))
    )
    (net (code "25") (name "/GND_G") (class "Default")
      (node (ref "RP2") (pin "34") (pinfunction "GND_G_34") (pintype "power_in"))
    )
    (net (code "26") (name "/GND_H") (class "Default")
      (node (ref "RP2") (pin "39") (pinfunction "GND_H_39") (pintype "power_in"))
    )
    (net (code "27") (name "/PRESENCE_1") (class "Default")
      (node (ref "JP3") (pin "1") (pinfunction "1_1") (pintype "passive"))
      (node (ref "U1") (pin "D8") (pinfunction "D8_D8") (pintype "bidirectional"))
    )
    (net (code "28") (name "/PRESENCE_2") (class "Default")
      (node (ref "JP4") (pin "1") (pinfunction "1_1") (pintype "passive"))
      (node (ref "U1") (pin "D9") (pinfunction "*D9_D9") (pintype "bidirectional"))
    )
    (net (code "29") (name "/PRESENCE_3") (class "Default")
      (node (ref "JP5") (pin "1") (pinfunction "1_1") (pintype "passive"))
      (node (ref "U1") (pin "D10") (pinfunction "*D10_D10") (pintype "bidirectional"))
    )
    (net (code "30") (name "/PRESENCE_4") (class "Default")
      (node (ref "JP6") (pin "1") (pinfunction "1_1") (pintype "passive"))
      (node (ref "U1") (pin "D11") (pinfunction "*D11_D11") (pintype "bidirectional"))
    )
    (net (code "31") (name "/PRESENCE_5") (class "Default")
      (node (ref "JP7") (pin "1") (pinfunction "1_1") (pintype "passive"))
      (node (ref "U1") (pin "D12") (pinfunction "D12_D12") (pintype "bidirectional"))
    )
    (net (code "32") (name "/PWM0") (class "Default")
      (node (ref "SRV0") (pin "3") (pinfunction "3_3") (pintype "passive"))
      (node (ref "U$1") (pin "P2") (pinfunction "PWM0_P2") (pintype "bidirectional"))
    )
    (net (code "33") (name "/PWM1") (class "Default")
      (node (ref "SRV1") (pin "3") (pinfunction "3_3") (pintype "passive"))
      (node (ref "U$1") (pin "P3") (pinfunction "PWM1_P3") (pintype "bidirectional"))
    )
    (net (code "34") (name "/PWM2") (class "Default")
      (node (ref "SRV2") (pin "3") (pinfunction "3_3") (pintype "passive"))
      (node (ref "U$1") (pin "P4") (pinfunction "PWM2_P4") (pintype "bidirectional"))
    )
    (net (code "35") (name "/PWM3") (class "Default")
      (node (ref "SRV3") (pin "3") (pinfunction "3_3") (pintype "passive"))
      (node (ref "U$1") (pin "P5") (pinfunction "PWM3_P5") (pintype "bidirectional"))
    )
    (net (code "36") (name "/PWM4") (class "Default")
      (node (ref "SRV4") (pin "3") (pinfunction "3_3") (pintype "passive"))
      (node (ref "U$1") (pin "P6") (pinfunction "PWM4_P6") (pintype "bidirectional"))
    )
    (net (code "37") (name "/PWM5") (class "Default")
      (node (ref "SRV5") (pin "3") (pinfunction "3_3") (pintype "passive"))
      (node (ref "U$1") (pin "P7") (pinfunction "PWM5_P7") (pintype "bidirectional"))
    )
    (net (code "38") (name "/PWM6") (class "Default")
      (node (ref "SRV6") (pin "3") (pinfunction "3_3") (pintype "passive"))
      (node (ref "U$1") (pin "P8") (pinfunction "PWM6_P8") (pintype "bidirectional"))
    )
    (net (code "39") (name "/PWM7") (class "Default")
      (node (ref "SRV7") (pin "3") (pinfunction "3_3") (pintype "passive"))
      (node (ref "U$1") (pin "P9") (pinfunction "PWM7_P9") (pintype "bidirectional"))
    )
    (net (code "40") (name "/PWM8") (class "Default")
      (node (ref "SRV8") (pin "3") (pinfunction "3_3") (pintype "passive"))
      (node (ref "U$1") (pin "P10") (pinfunction "PWM8_P10") (pintype "bidirectional"))
    )
    (net (code "41") (name "/PWM9") (class "Default")
      (node (ref "SRV9") (pin "3") (pinfunction "3_3") (pintype "passive"))
      (node (ref "U$1") (pin "P11") (pinfunction "PWM9_P11") (pintype "bidirectional"))
    )
    (net (code "42") (name "/PWM10") (class "Default")
      (node (ref "SRV10") (pin "3") (pinfunction "3_3") (pintype "passive"))
      (node (ref "U$1") (pin "P12") (pinfunction "PWM10_P12") (pintype "bidirectional"))
    )
    (net (code "43") (name "/PWM11") (class "Default")
      (node (ref "SRV11") (pin "3") (pinfunction "3_3") (pintype "passive"))
      (node (ref "U$1") (pin "P13") (pinfunction "PWM11_P13") (pintype "bidirectional"))
    )
    (net (code "44") (name "/PWM12") (class "Default")
      (node (ref "SRV12") (pin "3") (pinfunction "3_3") (pintype "passive"))
      (node (ref "U$1") (pin "P17") (pinfunction "PWM12_P17") (pintype "bidirectional"))
    )
    (net (code "45") (name "/PWM13") (class "Default")
      (node (ref "SRV13") (pin "3") (pinfunction "3_3") (pintype "passive"))
      (node (ref "U$1") (pin "P16") (pinfunction "PWM13_P16") (pintype "bidirectional"))
    )
    (net (code "46") (name "/PWM14") (class "Default")
      (node (ref "SRV14") (pin "3") (pinfunction "3_3") (pintype "passive"))
      (node (ref "U$1") (pin "P15") (pinfunction "PWM14_P15") (pintype "bidirectional"))
    )
    (net (code "47") (name "/PWM15") (class "Default")
      (node (ref "SRV15") (pin "3") (pinfunction "3_3") (pintype "passive"))
      (node (ref "U$1") (pin "P14") (pinfunction "PWM15_P14") (pintype "bidirectional"))
    )
    (net (code "48") (name "/RX_RP2") (class "Default")
      (node (ref "CON_UARTRP2") (pin "1") (pinfunction "1_1") (pintype "passive"))
      (node (ref "RP2") (pin "10") (pinfunction "RXD_10") (pintype "bidirectional"))
    )
    (net (code "49") (name "/SCL_ARDU") (class "Default")
      (node (ref "CON_I2CARDU") (pin "1") (pinfunction "1_1") (pintype "passive"))
      (node (ref "CON_I2CARDU_1") (pin "1") (pinfunction "1_1") (pintype "passive"))
      (node (ref "U1") (pin "A5") (pinfunction "A5_A5") (pintype "bidirectional"))
    )
    (net (code "50") (name "/SCL_RP1") (class "Default")
      (node (ref "CON_I2CRP2") (pin "1") (pinfunction "1_1") (pintype "passive"))
      (node (ref "CON_I2CRP2_2") (pin "1") (pinfunction "1_1") (pintype "passive"))
      (node (ref "RP2") (pin "5") (pinfunction "SCL_5") (pintype "bidirectional"))
    )
    (net (code "51") (name "/SCL_SERVOS") (class "Default")
      (node (ref "CON_I2C_SERVOS") (pin "1") (pinfunction "1_1") (pintype "passive"))
      (node (ref "P-UP_SCL") (pin "2") (pinfunction "2_2") (pintype "passive"))
      (node (ref "U$1") (pin "P18") (pinfunction "SCL_P18") (pintype "bidirectional"))
    )
    (net (code "52") (name "/SCL_SONARS") (class "Default")
      (node (ref "CON_I2C_SONARS") (pin "2") (pinfunction "2_2") (pintype "passive"))
      (node (ref "SV1") (pin "3") (pinfunction "3_3") (pintype "passive"))
      (node (ref "SV10") (pin "3") (pinfunction "3_3") (pintype "passive"))
      (node (ref "SV11") (pin "3") (pinfunction "3_3") (pintype "passive"))
      (node (ref "SV12") (pin "3") (pinfunction "3_3") (pintype "passive"))
      (node (ref "SV2") (pin "3") (pinfunction "3_3") (pintype "passive"))
      (node (ref "SV3") (pin "3") (pinfunction "3_3") (pintype "passive"))
      (node (ref "SV4") (pin "3") (pinfunction "3_3") (pintype "passive"))
      (node (ref "SV5") (pin "3") (pinfunction "3_3") (pintype "passive"))
      (node (ref "SV6") (pin "3") (pinfunction "3_3") (pintype "passive"))
      (node (ref "SV7") (pin "3") (pinfunction "3_3") (pintype "passive"))
      (node (ref "SV8") (pin "3") (pinfunction "3_3") (pintype "passive"))
      (node (ref "SV9") (pin "3") (pinfunction "3_3") (pintype "passive"))
      (node (ref "SV9-1") (pin "3") (pinfunction "3_3") (pintype "passive"))
    )
    (net (code "53") (name "/SDA_ARDU") (class "Default")
      (node (ref "CON_I2CARDU") (pin "2") (pinfunction "2_2") (pintype "passive"))
      (node (ref "CON_I2CARDU_1") (pin "2") (pinfunction "2_2") (pintype "passive"))
      (node (ref "U1") (pin "A4") (pinfunction "A4_A4") (pintype "bidirectional"))
    )
    (net (code "54") (name "/SDA_RP1") (class "Default")
      (node (ref "CON_I2CRP2") (pin "2") (pinfunction "2_2") (pintype "passive"))
      (node (ref "CON_I2CRP2_2") (pin "2") (pinfunction "2_2") (pintype "passive"))
      (node (ref "RP2") (pin "3") (pinfunction "SDA_3") (pintype "bidirectional"))
    )
    (net (code "55") (name "/SDA_SERVOS") (class "Default")
      (node (ref "CON_I2C_SERVOS") (pin "2") (pinfunction "2_2") (pintype "passive"))
      (node (ref "P-UP_SDA") (pin "1") (pinfunction "1_1") (pintype "passive"))
      (node (ref "U$1") (pin "P19") (pinfunction "SDA_P19") (pintype "bidirectional"))
    )
    (net (code "56") (name "/SDA_SONARS") (class "Default")
      (node (ref "CON_I2C_SONARS") (pin "1") (pinfunction "1_1") (pintype "passive"))
      (node (ref "SV1") (pin "4") (pinfunction "4_4") (pintype "passive"))
      (node (ref "SV10") (pin "4") (pinfunction "4_4") (pintype "passive"))
      (node (ref "SV11") (pin "4") (pinfunction "4_4") (pintype "passive"))
      (node (ref "SV12") (pin "4") (pinfunction "4_4") (pintype "passive"))
      (node (ref "SV2") (pin "4") (pinfunction "4_4") (pintype "passive"))
      (node (ref "SV3") (pin "4") (pinfunction "4_4") (pintype "passive"))
      (node (ref "SV4") (pin "4") (pinfunction "4_4") (pintype "passive"))
      (node (ref "SV5") (pin "4") (pinfunction "4_4") (pintype "passive"))
      (node (ref "SV6") (pin "4") (pinfunction "4_4") (pintype "passive"))
      (node (ref "SV7") (pin "4") (pinfunction "4_4") (pintype "passive"))
      (node (ref "SV8") (pin "4") (pinfunction "4_4") (pintype "passive"))
      (node (ref "SV9") (pin "4") (pinfunction "4_4") (pintype "passive"))
      (node (ref "SV9-1") (pin "4") (pinfunction "4_4") (pintype "passive"))
    )
    (net (code "57") (name "/TX_RP2") (class "Default")
      (node (ref "CON_UARTRP2") (pin "2") (pinfunction "2_2") (pintype "passive"))
      (node (ref "RP2") (pin "8") (pinfunction "TXD_8") (pintype "bidirectional"))
    )
    (net (code "58") (name "Net-(3V3_PWR1B-KL)") (class "Default")
      (node (ref "3V3_PWR") (pin "2") (pinfunction "KL_2") (pintype "passive"))
      (node (ref "3V3_PWR1") (pin "2") (pinfunction "KL_2") (pintype "passive"))
      (node (ref "3V3_PWR2") (pin "2") (pinfunction "KL_2") (pintype "passive"))
      (node (ref "C2") (pin "1") (pinfunction "1_1") (pintype "passive"))
      (node (ref "REGU_3V3") (pin "3") (pinfunction "VO_3") (pintype "passive"))
    )
    (net (code "59") (name "Net-(12V_BOARDS1A-KL)") (class "Default")
      (node (ref "12V_BOARDS1") (pin "1") (pinfunction "KL_1") (pintype "passive"))
      (node (ref "12V_SIG_BOARDS") (pin "1") (pinfunction "KL_1") (pintype "passive"))
      (node (ref "C3") (pin "+") (pinfunction "+_+") (pintype "passive"))
      (node (ref "U$2") (pin "1") (pinfunction "+VIN_1") (pintype "bidirectional"))
    )
    (net (code "60") (name "Net-(12V_BOARDS1B-KL)") (class "Default")
      (node (ref "12V_BOARDS1") (pin "2") (pinfunction "KL_2") (pintype "passive"))
      (node (ref "12V_SIG_BOARDS") (pin "2") (pinfunction "KL_2") (pintype "passive"))
      (node (ref "C3") (pin "-") (pinfunction "-_-") (pintype "passive"))
      (node (ref "U$2") (pin "2") (pinfunction "-VIN_2") (pintype "bidirectional"))
    )
    (net (code "61") (name "Net-(12V_BOARDS_SRCA-KL)") (class "Default")
      (node (ref "12V_BOARDS_SRC") (pin "1") (pinfunction "KL_1") (pintype "passive"))
      (node (ref "LED5") (pin "A") (pinfunction "A_A") (pintype "passive"))
      (node (ref "U$8") (pin "P$2") (pinfunction "P$2_P$2") (pintype "bidirectional"))
    )
    (net (code "62") (name "Net-(12V_PWR_BOARD1A-KL)") (class "Default")
      (node (ref "12V_PWR_BOARD") (pin "1") (pinfunction "KL_1") (pintype "passive"))
      (node (ref "12V_PWR_BOARD1") (pin "1") (pinfunction "KL_1") (pintype "passive"))
      (node (ref "12V_PWR_BOARD2") (pin "1") (pinfunction "KL_1") (pintype "passive"))
      (node (ref "C1") (pin "1") (pinfunction "1_1") (pintype "passive"))
      (node (ref "REGU_3V3") (pin "1") (pinfunction "VI_1") (pintype "input"))
    )
    (net (code "63") (name "Net-(12V_PWR_SRCA-KL)") (class "Default")
      (node (ref "12V_PWR_SRC") (pin "1") (pinfunction "KL_1") (pintype "passive"))
      (node (ref "LED4") (pin "A") (pinfunction "A_A") (pintype "passive"))
      (node (ref "U$6") (pin "P$2") (pinfunction "P$2_P$2") (pintype "bidirectional"))
    )
    (net (code "64") (name "Net-(BOARDIHM_CON_IHM-Pad1)") (class "Default")
      (node (ref "BOARDIHM_CON_IHM") (pin "1") (pinfunction "1_1") (pintype "passive"))
      (node (ref "U$9") (pin "P$1") (pinfunction "P$1_P$1") (pintype "bidirectional"))
    )
    (net (code "65") (name "Net-(BOARDIHM_CON_IHM-Pad4)") (class "Default")
      (node (ref "BOARDIHM_CON_IHM") (pin "4") (pinfunction "4_4") (pintype "passive"))
      (node (ref "U$10") (pin "P$1") (pinfunction "P$1_P$1") (pintype "bidirectional"))
    )
    (net (code "66") (name "Net-(BOARDIHM_CON_IHM-Pad7)") (class "Default")
      (node (ref "BOARDIHM_CON_IHM") (pin "7") (pinfunction "7_7") (pintype "passive"))
      (node (ref "U$12") (pin "P$1") (pinfunction "P$1_P$1") (pintype "bidirectional"))
    )
    (net (code "67") (name "Net-(CON_UARTARDU-Pad4)") (class "Default")
      (node (ref "CON_UARTARDU") (pin "4") (pinfunction "4_4") (pintype "passive"))
      (node (ref "JP1") (pin "1") (pinfunction "1_1") (pintype "passive"))
    )
    (net (code "68") (name "Net-(IHM-Pad1)") (class "Default")
      (node (ref "IHM") (pin "1") (pinfunction "1_1") (pintype "passive"))
      (node (ref "U1") (pin "D7") (pinfunction "D7_D7") (pintype "bidirectional"))
    )
    (net (code "69") (name "Net-(IHM-Pad4)") (class "Default")
      (node (ref "IHM") (pin "4") (pinfunction "4_4") (pintype "passive"))
      (node (ref "U1") (pin "D4") (pinfunction "D4_D4") (pintype "bidirectional"))
    )
    (net (code "70") (name "Net-(IHM-Pad7)") (class "Default")
      (node (ref "IHM") (pin "7") (pinfunction "7_7") (pintype "passive"))
      (node (ref "U1") (pin "D2") (pinfunction "D2_D2") (pintype "bidirectional"))
    )
    (net (code "71") (name "Net-(LED1-C)") (class "Default")
      (node (ref "LED1") (pin "K") (pinfunction "C_K") (pintype "passive"))
      (node (ref "R3") (pin "P$1") (pinfunction "1_P$1") (pintype "passive"))
    )
    (net (code "72") (name "Net-(LED2-C)") (class "Default")
      (node (ref "LED2") (pin "K") (pinfunction "C_K") (pintype "passive"))
      (node (ref "R1") (pin "P$2") (pinfunction "2_P$2") (pintype "passive"))
    )
    (net (code "73") (name "Net-(LED2-PadA)") (class "Default")
      (node (ref "LED2") (pin "A") (pinfunction "A_A") (pintype "passive"))
      (node (ref "U1") (pin "D13") (pinfunction "D13_D13") (pintype "bidirectional"))
    )
    (net (code "74") (name "Net-(LED3-C)") (class "Default")
      (node (ref "LED3") (pin "K") (pinfunction "C_K") (pintype "passive"))
      (node (ref "R2") (pin "P$2") (pinfunction "2_P$2") (pintype "passive"))
    )
    (net (code "75") (name "Net-(LED4-C)") (class "Default")
      (node (ref "LED4") (pin "K") (pinfunction "C_K") (pintype "passive"))
      (node (ref "R19") (pin "P$1") (pinfunction "1_P$1") (pintype "passive"))
    )
    (net (code "76") (name "Net-(LED5-C)") (class "Default")
      (node (ref "LED5") (pin "K") (pinfunction "C_K") (pintype "passive"))
      (node (ref "R20") (pin "P$1") (pinfunction "1_P$1") (pintype "passive"))
    )
    (net (code "77") (name "Net-(LED6-BLUE)") (class "Default")
      (node (ref "BOARDIHM_CON_IHM") (pin "6") (pinfunction "6_6") (pintype "passive"))
      (node (ref "LED6") (pin "4") (pinfunction "BLUE_4") (pintype "bidirectional"))
    )
    (net (code "78") (name "Net-(LED6-GREEN)") (class "Default")
      (node (ref "BOARDIHM_CON_IHM") (pin "5") (pinfunction "5_5") (pintype "passive"))
      (node (ref "LED6") (pin "3") (pinfunction "GREEN_3") (pintype "bidirectional"))
    )
    (net (code "79") (name "Net-(LED6-RED)") (class "Default")
      (node (ref "BOARDIHM_CON_IHM") (pin "2") (pinfunction "2_2") (pintype "passive"))
      (node (ref "LED6") (pin "1") (pinfunction "RED_1") (pintype "bidirectional"))
    )
    (net (code "80") (name "Net-(R4-1)") (class "Default")
      (node (ref "P-UP_SDA") (pin "2") (pinfunction "2_2") (pintype "passive"))
      (node (ref "R4") (pin "P$1") (pinfunction "1_P$1") (pintype "passive"))
    )
    (net (code "81") (name "Net-(R7-1)") (class "Default")
      (node (ref "P-UP_SCL") (pin "1") (pinfunction "1_1") (pintype "passive"))
      (node (ref "R7") (pin "P$1") (pinfunction "1_P$1") (pintype "passive"))
    )
    (net (code "82") (name "Net-(R8-1)") (class "Default")
      (node (ref "IHM") (pin "2") (pinfunction "2_2") (pintype "passive"))
      (node (ref "R8") (pin "P$1") (pinfunction "1_P$1") (pintype "passive"))
    )
    (net (code "83") (name "Net-(R8-2)") (class "Default")
      (node (ref "R8") (pin "P$2") (pinfunction "2_P$2") (pintype "passive"))
      (node (ref "U1") (pin "D6") (pinfunction "*D6_D6") (pintype "bidirectional"))
    )
    (net (code "84") (name "Net-(R9-1)") (class "Default")
      (node (ref "IHM") (pin "6") (pinfunction "6_6") (pintype "passive"))
      (node (ref "R9") (pin "P$1") (pinfunction "1_P$1") (pintype "passive"))
    )
    (net (code "85") (name "Net-(R9-2)") (class "Default")
      (node (ref "R9") (pin "P$2") (pinfunction "2_P$2") (pintype "passive"))
      (node (ref "U1") (pin "D3") (pinfunction "*D3_D3") (pintype "bidirectional"))
    )
    (net (code "86") (name "Net-(R10-1)") (class "Default")
      (node (ref "IHM") (pin "5") (pinfunction "5_5") (pintype "passive"))
      (node (ref "R10") (pin "P$1") (pinfunction "1_P$1") (pintype "passive"))
    )
    (net (code "87") (name "Net-(R10-2)") (class "Default")
      (node (ref "R10") (pin "P$2") (pinfunction "2_P$2") (pintype "passive"))
      (node (ref "U1") (pin "D5") (pinfunction "*D5_D5") (pintype "bidirectional"))
    )
    (net (code "88") (name "Net-(RP2-GPIO04)") (class "Default")
      (node (ref "LED3") (pin "A") (pinfunction "A_A") (pintype "passive"))
      (node (ref "RP2") (pin "7") (pinfunction "GPIO04_7") (pintype "bidirectional"))
    )
    (net (code "89") (name "Net-(RP2-SPI_CE1)") (class "Default")
      (node (ref "PWR_RP2") (pin "2") (pinfunction "2_2") (pintype "passive"))
      (node (ref "RP2") (pin "26") (pinfunction "SPI_CE1_26") (pintype "bidirectional"))
    )
    (net (code "90") (name "Net-(U$2-TRM)") (class "Default")
      (node (ref "R5") (pin "2") (pinfunction "2_2") (pintype "passive"))
      (node (ref "R6") (pin "2") (pinfunction "2_2") (pintype "passive"))
      (node (ref "U$2") (pin "7") (pinfunction "TRM_7") (pintype "bidirectional"))
    )
    (net (code "91") (name "Net-(U$4-P$2)") (class "Default")
      (node (ref "U$4") (pin "P2") (pinfunction "P$2_P2") (pintype "bidirectional"))
      (node (ref "U$6") (pin "P$1") (pinfunction "P$1_P$1") (pintype "bidirectional"))
    )
    (net (code "92") (name "unconnected-(IHM-Pad8)") (class "Default")
      (node (ref "IHM") (pin "8") (pinfunction "8_8") (pintype "passive"))
    )
    (net (code "93") (name "unconnected-(JP1-Pad3)") (class "Default")
      (node (ref "JP1") (pin "3") (pinfunction "3_3") (pintype "passive"))
    )
    (net (code "94") (name "unconnected-(JP2-Pad3)") (class "Default")
      (node (ref "JP2") (pin "3") (pinfunction "3_3") (pintype "passive"))
    )
    (net (code "95") (name "unconnected-(JP8-Pad1)") (class "Default")
      (node (ref "JP8") (pin "1") (pinfunction "1_1") (pintype "passive"))
    )
    (net (code "96") (name "unconnected-(JP9-Pad1)") (class "Default")
      (node (ref "JP9") (pin "1") (pinfunction "1_1") (pintype "passive"))
    )
    (net (code "97") (name "unconnected-(PWR_RP2-Pad1)") (class "Default")
      (node (ref "PWR_RP2") (pin "1") (pinfunction "1_1") (pintype "passive"))
    )
    (net (code "98") (name "unconnected-(PWR_RP2-Pad3)") (class "Default")
      (node (ref "PWR_RP2") (pin "3") (pinfunction "3_3") (pintype "passive"))
    )
    (net (code "99") (name "unconnected-(RP2-GPIO05-Pad29)") (class "Default")
      (node (ref "RP2") (pin "29") (pinfunction "GPIO05_29") (pintype "no_connect"))
    )
    (net (code "100") (name "unconnected-(RP2-GPIO06-Pad31)") (class "Default")
      (node (ref "RP2") (pin "31") (pinfunction "GPIO06_31") (pintype "no_connect"))
    )
    (net (code "101") (name "unconnected-(RP2-GPIO12-Pad32)") (class "Default")
      (node (ref "RP2") (pin "32") (pinfunction "GPIO12_32") (pintype "no_connect"))
    )
    (net (code "102") (name "unconnected-(RP2-GPIO13-Pad33)") (class "Default")
      (node (ref "RP2") (pin "33") (pinfunction "GPIO13_33") (pintype "no_connect"))
    )
    (net (code "103") (name "unconnected-(RP2-GPIO16-Pad36)") (class "Default")
      (node (ref "RP2") (pin "36") (pinfunction "GPIO16_36") (pintype "no_connect"))
    )
    (net (code "104") (name "unconnected-(RP2-GPIO17-Pad11)") (class "Default")
      (node (ref "RP2") (pin "11") (pinfunction "GPIO17_11") (pintype "bidirectional"))
    )
    (net (code "105") (name "unconnected-(RP2-GPIO18-Pad12)") (class "Default")
      (node (ref "RP2") (pin "12") (pinfunction "GPIO18_12") (pintype "bidirectional"))
    )
    (net (code "106") (name "unconnected-(RP2-GPIO19-Pad35)") (class "Default")
      (node (ref "RP2") (pin "35") (pinfunction "GPIO19_35") (pintype "no_connect"))
    )
    (net (code "107") (name "unconnected-(RP2-GPIO20-Pad38)") (class "Default")
      (node (ref "RP2") (pin "38") (pinfunction "GPIO20_38") (pintype "no_connect"))
    )
    (net (code "108") (name "unconnected-(RP2-GPIO21-Pad40)") (class "Default")
      (node (ref "RP2") (pin "40") (pinfunction "GPIO21_40") (pintype "no_connect"))
    )
    (net (code "109") (name "unconnected-(RP2-GPIO22-Pad15)") (class "Default")
      (node (ref "RP2") (pin "15") (pinfunction "GPIO22_15") (pintype "bidirectional"))
    )
    (net (code "110") (name "unconnected-(RP2-GPIO23-Pad16)") (class "Default")
      (node (ref "RP2") (pin "16") (pinfunction "GPIO23_16") (pintype "bidirectional"))
    )
    (net (code "111") (name "unconnected-(RP2-GPIO24-Pad18)") (class "Default")
      (node (ref "RP2") (pin "18") (pinfunction "GPIO24_18") (pintype "bidirectional"))
    )
    (net (code "112") (name "unconnected-(RP2-GPIO25-Pad22)") (class "Default")
      (node (ref "RP2") (pin "22") (pinfunction "GPIO25_22") (pintype "bidirectional"))
    )
    (net (code "113") (name "unconnected-(RP2-GPIO26-Pad37)") (class "Default")
      (node (ref "RP2") (pin "37") (pinfunction "GPIO26_37") (pintype "no_connect"))
    )
    (net (code "114") (name "unconnected-(RP2-GPIO27-Pad13)") (class "Default")
      (node (ref "RP2") (pin "13") (pinfunction "GPIO27_13") (pintype "bidirectional"))
    )
    (net (code "115") (name "unconnected-(RP2-ID_SC-Pad28)") (class "Default")
      (node (ref "RP2") (pin "28") (pinfunction "ID_SC_28") (pintype "no_connect"))
    )
    (net (code "116") (name "unconnected-(RP2-ID_SD-Pad27)") (class "Default")
      (node (ref "RP2") (pin "27") (pinfunction "ID_SD_27") (pintype "no_connect"))
    )
    (net (code "117") (name "unconnected-(RP2-PadRUN1)") (class "Default")
      (node (ref "RP2") (pin "RUN1") (pinfunction "RUN1_RUN1") (pintype "bidirectional"))
    )
    (net (code "118") (name "unconnected-(RP2-PadRUN2)") (class "Default")
      (node (ref "RP2") (pin "RUN2") (pinfunction "RUN2_RUN2") (pintype "bidirectional"))
    )
    (net (code "119") (name "unconnected-(RP2-SPI_CE0-Pad24)") (class "Default")
      (node (ref "RP2") (pin "24") (pinfunction "SPI_CE0_24") (pintype "bidirectional"))
    )
    (net (code "120") (name "unconnected-(RP2-SPI_MISO-Pad21)") (class "Default")
      (node (ref "RP2") (pin "21") (pinfunction "SPI_MISO_21") (pintype "bidirectional"))
    )
    (net (code "121") (name "unconnected-(RP2-SPI_MOSI-Pad19)") (class "Default")
      (node (ref "RP2") (pin "19") (pinfunction "SPI_MOSI_19") (pintype "bidirectional"))
    )
    (net (code "122") (name "unconnected-(RP2-SPI_SCLK-Pad23)") (class "Default")
      (node (ref "RP2") (pin "23") (pinfunction "SPI_SCLK_23") (pintype "bidirectional"))
    )
    (net (code "123") (name "unconnected-(SV1-Pad2)") (class "Default")
      (node (ref "SV1") (pin "2") (pinfunction "2_2") (pintype "passive"))
    )
    (net (code "124") (name "unconnected-(SV2-Pad2)") (class "Default")
      (node (ref "SV2") (pin "2") (pinfunction "2_2") (pintype "passive"))
    )
    (net (code "125") (name "unconnected-(SV3-Pad2)") (class "Default")
      (node (ref "SV3") (pin "2") (pinfunction "2_2") (pintype "passive"))
    )
    (net (code "126") (name "unconnected-(SV4-Pad2)") (class "Default")
      (node (ref "SV4") (pin "2") (pinfunction "2_2") (pintype "passive"))
    )
    (net (code "127") (name "unconnected-(SV5-Pad2)") (class "Default")
      (node (ref "SV5") (pin "2") (pinfunction "2_2") (pintype "passive"))
    )
    (net (code "128") (name "unconnected-(SV6-Pad2)") (class "Default")
      (node (ref "SV6") (pin "2") (pinfunction "2_2") (pintype "passive"))
    )
    (net (code "129") (name "unconnected-(SV7-Pad2)") (class "Default")
      (node (ref "SV7") (pin "2") (pinfunction "2_2") (pintype "passive"))
    )
    (net (code "130") (name "unconnected-(SV8-Pad2)") (class "Default")
      (node (ref "SV8") (pin "2") (pinfunction "2_2") (pintype "passive"))
    )
    (net (code "131") (name "unconnected-(SV9-1-Pad2)") (class "Default")
      (node (ref "SV9-1") (pin "2") (pinfunction "2_2") (pintype "passive"))
    )
    (net (code "132") (name "unconnected-(SV9-Pad2)") (class "Default")
      (node (ref "SV9") (pin "2") (pinfunction "2_2") (pintype "passive"))
    )
    (net (code "133") (name "unconnected-(SV10-Pad2)") (class "Default")
      (node (ref "SV10") (pin "2") (pinfunction "2_2") (pintype "passive"))
    )
    (net (code "134") (name "unconnected-(SV11-Pad2)") (class "Default")
      (node (ref "SV11") (pin "2") (pinfunction "2_2") (pintype "passive"))
    )
    (net (code "135") (name "unconnected-(SV12-Pad2)") (class "Default")
      (node (ref "SV12") (pin "2") (pinfunction "2_2") (pintype "passive"))
    )
    (net (code "136") (name "unconnected-(U$2-ON{slash}OFF-Pad3)") (class "Default")
      (node (ref "U$2") (pin "3") (pinfunction "ON/OFF_3") (pintype "bidirectional"))
    )
    (net (code "137") (name "unconnected-(U$5-5V-PadP20)") (class "Default")
      (node (ref "U$5") (pin "P20") (pinfunction "5V_P20") (pintype "bidirectional"))
    )
    (net (code "138") (name "unconnected-(U$5-GND-PadP1)") (class "Default")
      (node (ref "U$5") (pin "P1") (pinfunction "GND_P1") (pintype "bidirectional"))
    )
    (net (code "139") (name "unconnected-(U$5-PWM0-PadP2)") (class "Default")
      (node (ref "U$5") (pin "P2") (pinfunction "PWM0_P2") (pintype "bidirectional"))
    )
    (net (code "140") (name "unconnected-(U$5-PWM1-PadP3)") (class "Default")
      (node (ref "U$5") (pin "P3") (pinfunction "PWM1_P3") (pintype "bidirectional"))
    )
    (net (code "141") (name "unconnected-(U$5-PWM2-PadP4)") (class "Default")
      (node (ref "U$5") (pin "P4") (pinfunction "PWM2_P4") (pintype "bidirectional"))
    )
    (net (code "142") (name "unconnected-(U$5-PWM3-PadP5)") (class "Default")
      (node (ref "U$5") (pin "P5") (pinfunction "PWM3_P5") (pintype "bidirectional"))
    )
    (net (code "143") (name "unconnected-(U$5-PWM4-PadP6)") (class "Default")
      (node (ref "U$5") (pin "P6") (pinfunction "PWM4_P6") (pintype "bidirectional"))
    )
    (net (code "144") (name "unconnected-(U$5-PWM5-PadP7)") (class "Default")
      (node (ref "U$5") (pin "P7") (pinfunction "PWM5_P7") (pintype "bidirectional"))
    )
    (net (code "145") (name "unconnected-(U$5-PWM6-PadP8)") (class "Default")
      (node (ref "U$5") (pin "P8") (pinfunction "PWM6_P8") (pintype "bidirectional"))
    )
    (net (code "146") (name "unconnected-(U$5-PWM7-PadP9)") (class "Default")
      (node (ref "U$5") (pin "P9") (pinfunction "PWM7_P9") (pintype "bidirectional"))
    )
    (net (code "147") (name "unconnected-(U$5-PWM8-PadP10)") (class "Default")
      (node (ref "U$5") (pin "P10") (pinfunction "PWM8_P10") (pintype "bidirectional"))
    )
    (net (code "148") (name "unconnected-(U$5-PWM9-PadP11)") (class "Default")
      (node (ref "U$5") (pin "P11") (pinfunction "PWM9_P11") (pintype "bidirectional"))
    )
    (net (code "149") (name "unconnected-(U$5-PWM10-PadP12)") (class "Default")
      (node (ref "U$5") (pin "P12") (pinfunction "PWM10_P12") (pintype "bidirectional"))
    )
    (net (code "150") (name "unconnected-(U$5-PWM11-PadP13)") (class "Default")
      (node (ref "U$5") (pin "P13") (pinfunction "PWM11_P13") (pintype "bidirectional"))
    )
    (net (code "151") (name "unconnected-(U$5-PWM12-PadP17)") (class "Default")
      (node (ref "U$5") (pin "P17") (pinfunction "PWM12_P17") (pintype "bidirectional"))
    )
    (net (code "152") (name "unconnected-(U$5-PWM13-PadP16)") (class "Default")
      (node (ref "U$5") (pin "P16") (pinfunction "PWM13_P16") (pintype "bidirectional"))
    )
    (net (code "153") (name "unconnected-(U$5-PWM14-PadP15)") (class "Default")
      (node (ref "U$5") (pin "P15") (pinfunction "PWM14_P15") (pintype "bidirectional"))
    )
    (net (code "154") (name "unconnected-(U$5-PWM15-PadP14)") (class "Default")
      (node (ref "U$5") (pin "P14") (pinfunction "PWM15_P14") (pintype "bidirectional"))
    )
    (net (code "155") (name "unconnected-(U$5-SCL-PadP18)") (class "Default")
      (node (ref "U$5") (pin "P18") (pinfunction "SCL_P18") (pintype "bidirectional"))
    )
    (net (code "156") (name "unconnected-(U$5-SDA-PadP19)") (class "Default")
      (node (ref "U$5") (pin "P19") (pinfunction "SDA_P19") (pintype "bidirectional"))
    )
    (net (code "157") (name "unconnected-(U$7-5V-PadP20)") (class "Default")
      (node (ref "U$7") (pin "P20") (pinfunction "5V_P20") (pintype "bidirectional"))
    )
    (net (code "158") (name "unconnected-(U$7-GND-PadP1)") (class "Default")
      (node (ref "U$7") (pin "P1") (pinfunction "GND_P1") (pintype "bidirectional"))
    )
    (net (code "159") (name "unconnected-(U$7-PWM0-PadP2)") (class "Default")
      (node (ref "U$7") (pin "P2") (pinfunction "PWM0_P2") (pintype "bidirectional"))
    )
    (net (code "160") (name "unconnected-(U$7-PWM1-PadP3)") (class "Default")
      (node (ref "U$7") (pin "P3") (pinfunction "PWM1_P3") (pintype "bidirectional"))
    )
    (net (code "161") (name "unconnected-(U$7-PWM2-PadP4)") (class "Default")
      (node (ref "U$7") (pin "P4") (pinfunction "PWM2_P4") (pintype "bidirectional"))
    )
    (net (code "162") (name "unconnected-(U$7-PWM3-PadP5)") (class "Default")
      (node (ref "U$7") (pin "P5") (pinfunction "PWM3_P5") (pintype "bidirectional"))
    )
    (net (code "163") (name "unconnected-(U$7-PWM4-PadP6)") (class "Default")
      (node (ref "U$7") (pin "P6") (pinfunction "PWM4_P6") (pintype "bidirectional"))
    )
    (net (code "164") (name "unconnected-(U$7-PWM5-PadP7)") (class "Default")
      (node (ref "U$7") (pin "P7") (pinfunction "PWM5_P7") (pintype "bidirectional"))
    )
    (net (code "165") (name "unconnected-(U$7-PWM6-PadP8)") (class "Default")
      (node (ref "U$7") (pin "P8") (pinfunction "PWM6_P8") (pintype "bidirectional"))
    )
    (net (code "166") (name "unconnected-(U$7-PWM7-PadP9)") (class "Default")
      (node (ref "U$7") (pin "P9") (pinfunction "PWM7_P9") (pintype "bidirectional"))
    )
    (net (code "167") (name "unconnected-(U$7-PWM8-PadP10)") (class "Default")
      (node (ref "U$7") (pin "P10") (pinfunction "PWM8_P10") (pintype "bidirectional"))
    )
    (net (code "168") (name "unconnected-(U$7-PWM9-PadP11)") (class "Default")
      (node (ref "U$7") (pin "P11") (pinfunction "PWM9_P11") (pintype "bidirectional"))
    )
    (net (code "169") (name "unconnected-(U$7-PWM10-PadP12)") (class "Default")
      (node (ref "U$7") (pin "P12") (pinfunction "PWM10_P12") (pintype "bidirectional"))
    )
    (net (code "170") (name "unconnected-(U$7-PWM11-PadP13)") (class "Default")
      (node (ref "U$7") (pin "P13") (pinfunction "PWM11_P13") (pintype "bidirectional"))
    )
    (net (code "171") (name "unconnected-(U$7-PWM12-PadP17)") (class "Default")
      (node (ref "U$7") (pin "P17") (pinfunction "PWM12_P17") (pintype "bidirectional"))
    )
    (net (code "172") (name "unconnected-(U$7-PWM13-PadP16)") (class "Default")
      (node (ref "U$7") (pin "P16") (pinfunction "PWM13_P16") (pintype "bidirectional"))
    )
    (net (code "173") (name "unconnected-(U$7-PWM14-PadP15)") (class "Default")
      (node (ref "U$7") (pin "P15") (pinfunction "PWM14_P15") (pintype "bidirectional"))
    )
    (net (code "174") (name "unconnected-(U$7-PWM15-PadP14)") (class "Default")
      (node (ref "U$7") (pin "P14") (pinfunction "PWM15_P14") (pintype "bidirectional"))
    )
    (net (code "175") (name "unconnected-(U$7-SCL-PadP18)") (class "Default")
      (node (ref "U$7") (pin "P18") (pinfunction "SCL_P18") (pintype "bidirectional"))
    )
    (net (code "176") (name "unconnected-(U$7-SDA-PadP19)") (class "Default")
      (node (ref "U$7") (pin "P19") (pinfunction "SDA_P19") (pintype "bidirectional"))
    )
    (net (code "177") (name "unconnected-(U$13-5V-PadP20)") (class "Default")
      (node (ref "U$13") (pin "P20") (pinfunction "5V_P20") (pintype "bidirectional"))
    )
    (net (code "178") (name "unconnected-(U$13-GND-PadP1)") (class "Default")
      (node (ref "U$13") (pin "P1") (pinfunction "GND_P1") (pintype "bidirectional"))
    )
    (net (code "179") (name "unconnected-(U$13-PWM0-PadP2)") (class "Default")
      (node (ref "U$13") (pin "P2") (pinfunction "PWM0_P2") (pintype "bidirectional"))
    )
    (net (code "180") (name "unconnected-(U$13-PWM1-PadP3)") (class "Default")
      (node (ref "U$13") (pin "P3") (pinfunction "PWM1_P3") (pintype "bidirectional"))
    )
    (net (code "181") (name "unconnected-(U$13-PWM2-PadP4)") (class "Default")
      (node (ref "U$13") (pin "P4") (pinfunction "PWM2_P4") (pintype "bidirectional"))
    )
    (net (code "182") (name "unconnected-(U$13-PWM3-PadP5)") (class "Default")
      (node (ref "U$13") (pin "P5") (pinfunction "PWM3_P5") (pintype "bidirectional"))
    )
    (net (code "183") (name "unconnected-(U$13-PWM4-PadP6)") (class "Default")
      (node (ref "U$13") (pin "P6") (pinfunction "PWM4_P6") (pintype "bidirectional"))
    )
    (net (code "184") (name "unconnected-(U$13-PWM5-PadP7)") (class "Default")
      (node (ref "U$13") (pin "P7") (pinfunction "PWM5_P7") (pintype "bidirectional"))
    )
    (net (code "185") (name "unconnected-(U$13-PWM6-PadP8)") (class "Default")
      (node (ref "U$13") (pin "P8") (pinfunction "PWM6_P8") (pintype "bidirectional"))
    )
    (net (code "186") (name "unconnected-(U$13-PWM7-PadP9)") (class "Default")
      (node (ref "U$13") (pin "P9") (pinfunction "PWM7_P9") (pintype "bidirectional"))
    )
    (net (code "187") (name "unconnected-(U$13-PWM8-PadP10)") (class "Default")
      (node (ref "U$13") (pin "P10") (pinfunction "PWM8_P10") (pintype "bidirectional"))
    )
    (net (code "188") (name "unconnected-(U$13-PWM9-PadP11)") (class "Default")
      (node (ref "U$13") (pin "P11") (pinfunction "PWM9_P11") (pintype "bidirectional"))
    )
    (net (code "189") (name "unconnected-(U$13-PWM10-PadP12)") (class "Default")
      (node (ref "U$13") (pin "P12") (pinfunction "PWM10_P12") (pintype "bidirectional"))
    )
    (net (code "190") (name "unconnected-(U$13-PWM11-PadP13)") (class "Default")
      (node (ref "U$13") (pin "P13") (pinfunction "PWM11_P13") (pintype "bidirectional"))
    )
    (net (code "191") (name "unconnected-(U$13-PWM12-PadP17)") (class "Default")
      (node (ref "U$13") (pin "P17") (pinfunction "PWM12_P17") (pintype "bidirectional"))
    )
    (net (code "192") (name "unconnected-(U$13-PWM13-PadP16)") (class "Default")
      (node (ref "U$13") (pin "P16") (pinfunction "PWM13_P16") (pintype "bidirectional"))
    )
    (net (code "193") (name "unconnected-(U$13-PWM14-PadP15)") (class "Default")
      (node (ref "U$13") (pin "P15") (pinfunction "PWM14_P15") (pintype "bidirectional"))
    )
    (net (code "194") (name "unconnected-(U$13-PWM15-PadP14)") (class "Default")
      (node (ref "U$13") (pin "P14") (pinfunction "PWM15_P14") (pintype "bidirectional"))
    )
    (net (code "195") (name "unconnected-(U$13-SCL-PadP18)") (class "Default")
      (node (ref "U$13") (pin "P18") (pinfunction "SCL_P18") (pintype "bidirectional"))
    )
    (net (code "196") (name "unconnected-(U$13-SDA-PadP19)") (class "Default")
      (node (ref "U$13") (pin "P19") (pinfunction "SDA_P19") (pintype "bidirectional"))
    )
    (net (code "197") (name "unconnected-(U1-Pad3.3V)") (class "Default")
      (node (ref "U1") (pin "3.3V") (pinfunction "3.3V_3.3V") (pintype "bidirectional"))
    )
    (net (code "198") (name "unconnected-(U1-PadA0)") (class "Default")
      (node (ref "U1") (pin "A0") (pinfunction "A0_A0") (pintype "bidirectional"))
    )
    (net (code "199") (name "unconnected-(U1-PadA1)") (class "Default")
      (node (ref "U1") (pin "A1") (pinfunction "A1_A1") (pintype "bidirectional"))
    )
    (net (code "200") (name "unconnected-(U1-PadA2)") (class "Default")
      (node (ref "U1") (pin "A2") (pinfunction "A2_A2") (pintype "bidirectional"))
    )
    (net (code "201") (name "unconnected-(U1-PadA3)") (class "Default")
      (node (ref "U1") (pin "A3") (pinfunction "A3_A3") (pintype "bidirectional"))
    )
    (net (code "202") (name "unconnected-(U1-PadAREF)") (class "Default")
      (node (ref "U1") (pin "AREF") (pinfunction "AREF_AREF") (pintype "bidirectional"))
    )
    (net (code "203") (name "unconnected-(U1-PadIOREF)") (class "Default")
      (node (ref "U1") (pin "IOREF") (pinfunction "IOREF_IOREF") (pintype "bidirectional"))
    )
    (net (code "204") (name "unconnected-(U1-PadRES)") (class "Default")
      (node (ref "U1") (pin "RES") (pinfunction "RES_RES") (pintype "bidirectional"))
    )
    (net (code "205") (name "unconnected-(U1-PadSCL)") (class "Default")
      (node (ref "U1") (pin "SCL") (pinfunction "SCL_SCL") (pintype "bidirectional"))
    )
    (net (code "206") (name "unconnected-(U1-PadSDA)") (class "Default")
      (node (ref "U1") (pin "SDA") (pinfunction "SDA_SDA") (pintype "bidirectional"))
    )
    (net (code "207") (name "unconnected-(U1-PadVIN)") (class "Default")
      (node (ref "U1") (pin "VIN") (pinfunction "VIN_VIN") (pintype "bidirectional"))
    )
  )
)
